# ArduOSD_Simple2222.net
KiCad netlist of a schematic drawn in EAGLE
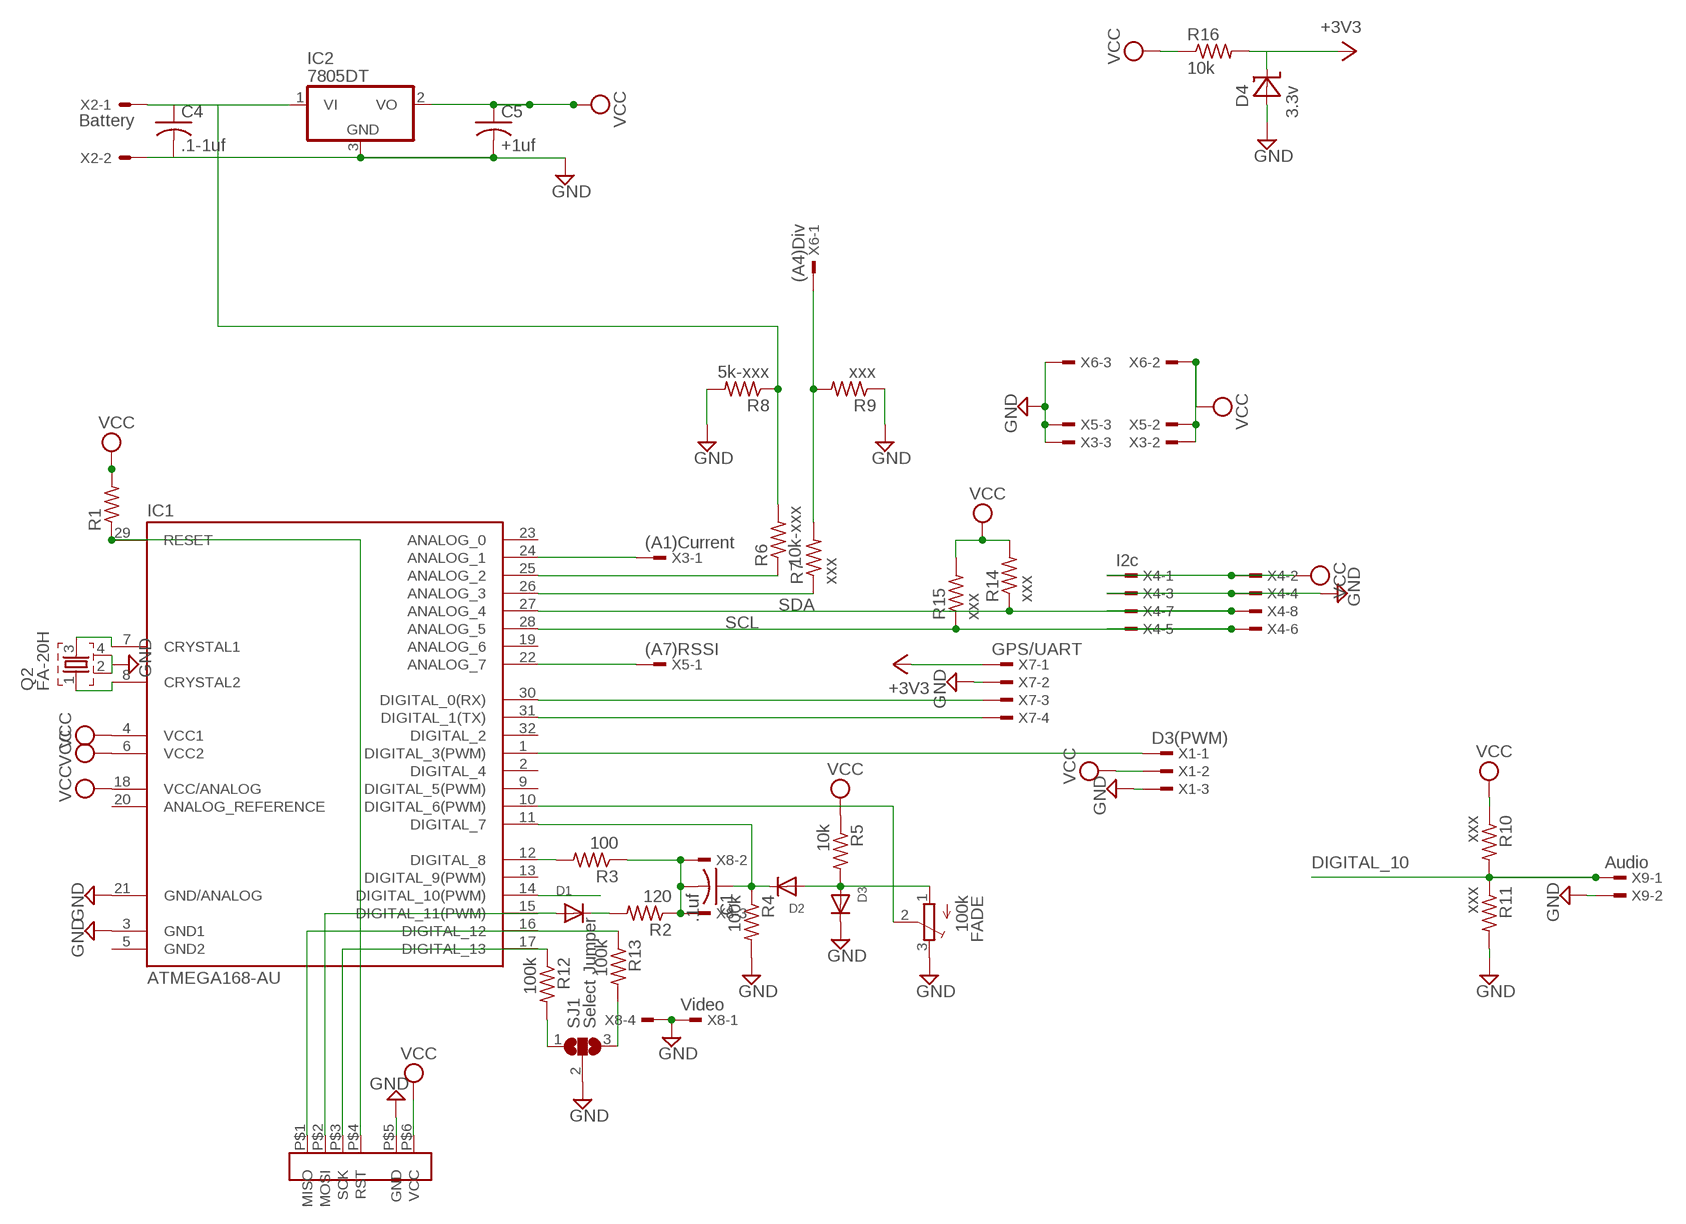
[diagram p0: schematic, sheet 1]

(export (version "E")
  (design (tool "Eeschema 10.0.6"))
  (components
    (comp (ref "C1")
      (value ".1uf")
      (footprint "eagle-import:C0805K")
      (libsource (lib "eagle-import") (part "C-USC0805K"))
    )
    (comp (ref "C4")
      (value ".1-1uf")
      (footprint "eagle-import:C0805K")
      (libsource (lib "eagle-import") (part "C-USC0805K"))
    )
    (comp (ref "C5")
      (value "+1uf")
      (footprint "eagle-import:C0805K")
      (libsource (lib "eagle-import") (part "C-USC0805K"))
    )
    (comp (ref "D1")
      (value "DIODESOT23_WAVE")
      (footprint "eagle-import:SOT23-W")
      (libsource (lib "eagle-import") (part "DIODESOT23_WAVE"))
    )
    (comp (ref "D2")
      (value "DIODESOT23_WAVE")
      (footprint "eagle-import:SOT23-W")
      (libsource (lib "eagle-import") (part "DIODESOT23_WAVE"))
    )
    (comp (ref "D3")
      (value "DIODESOT23_WAVE")
      (footprint "eagle-import:SOT23-W")
      (libsource (lib "eagle-import") (part "DIODESOT23_WAVE"))
    )
    (comp (ref "D4")
      (value "3.3v")
      (footprint "eagle-import:SOD-123")
      (libsource (lib "eagle-import") (part "ZENER_SOD123"))
    )
    (comp (ref "FADE")
      (value "100k")
      (footprint "eagle-import:TC33X")
      (libsource (lib "eagle-import") (part "TRIMPOTTC33X"))
    )
    (comp (ref "IC1")
      (value "ATMEGA168-AU")
      (footprint "eagle-import:TQFP32-08")
      (libsource (lib "eagle-import") (part "ATMEGA168-AU"))
    )
    (comp (ref "IC2")
      (value "7805DT")
      (footprint "eagle-import:TO252")
      (libsource (lib "eagle-import") (part "78DT05"))
    )
    (comp (ref "Q2")
      (value "FA-20H")
      (footprint "eagle-import:FA-20H")
      (libsource (lib "eagle-import") (part "FA-20H"))
    )
    (comp (ref "R1")
      (value "R-US_R0805")
      (footprint "eagle-import:R0805")
      (libsource (lib "eagle-import") (part "R-US_R0805"))
    )
    (comp (ref "R2")
      (value "120")
      (footprint "eagle-import:R0805")
      (libsource (lib "eagle-import") (part "R-US_R0805"))
    )
    (comp (ref "R3")
      (value "100")
      (footprint "eagle-import:R0805")
      (libsource (lib "eagle-import") (part "R-US_R0805"))
    )
    (comp (ref "R4")
      (value "100k")
      (footprint "eagle-import:R0805")
      (libsource (lib "eagle-import") (part "R-US_R0805"))
    )
    (comp (ref "R5")
      (value "10k")
      (footprint "eagle-import:R0805")
      (libsource (lib "eagle-import") (part "R-US_R0805"))
    )
    (comp (ref "R6")
      (value "10k-xxx")
      (footprint "eagle-import:R0805")
      (libsource (lib "eagle-import") (part "R-US_R0805"))
    )
    (comp (ref "R7")
      (value "xxx")
      (footprint "eagle-import:R0805")
      (libsource (lib "eagle-import") (part "R-US_R0805"))
    )
    (comp (ref "R8")
      (value "5k-xxx")
      (footprint "eagle-import:R0805")
      (libsource (lib "eagle-import") (part "R-US_R0805"))
    )
    (comp (ref "R9")
      (value "xxx")
      (footprint "eagle-import:R0805")
      (libsource (lib "eagle-import") (part "R-US_R0805"))
    )
    (comp (ref "R10")
      (value "xxx")
      (footprint "eagle-import:R0805")
      (libsource (lib "eagle-import") (part "R-US_R0805"))
    )
    (comp (ref "R11")
      (value "xxx")
      (footprint "eagle-import:R0805")
      (libsource (lib "eagle-import") (part "R-US_R0805"))
    )
    (comp (ref "R12")
      (value "100k")
      (footprint "eagle-import:R0805")
      (libsource (lib "eagle-import") (part "R-US_R0805"))
    )
    (comp (ref "R13")
      (value "100k")
      (footprint "eagle-import:R0805")
      (libsource (lib "eagle-import") (part "R-US_R0805"))
    )
    (comp (ref "R14")
      (value "xxx")
      (footprint "eagle-import:R0805")
      (libsource (lib "eagle-import") (part "R-US_R0805"))
    )
    (comp (ref "R15")
      (value "xxx")
      (footprint "eagle-import:R0805")
      (libsource (lib "eagle-import") (part "R-US_R0805"))
    )
    (comp (ref "R16")
      (value "10k")
      (footprint "eagle-import:R0805")
      (libsource (lib "eagle-import") (part "R-US_R0805"))
    )
    (comp (ref "SJ1")
      (value "Select Jumper")
      (footprint "eagle-import:SJ_2")
      (libsource (lib "eagle-import") (part "SJ2W"))
    )
    (comp (ref "U$1")
      (value "LIN_ISP")
      (footprint "eagle-import:LINEAR_ISP")
      (libsource (lib "eagle-import") (part "LIN_ISP"))
    )
    (comp (ref "X1")
      (value "D3(PWM)")
      (footprint "eagle-import:TSW-103-02-S-S")
      (fields (field (name "OC_FARNELL") "unknown") (field (name "OC_NEWARK") "unknown"))
      (libsource (lib "eagle-import") (part "TSW-103-02-S-S"))
    )
    (comp (ref "X2")
      (value "Battery")
      (footprint "eagle-import:22-23-2021")
      (fields (field (name "MF") "MOLEX") (field (name "MPN") "22-23-2021"))
      (libsource (lib "eagle-import") (part "22-23-2021"))
    )
    (comp (ref "X3")
      (value "(A1)Current")
      (footprint "eagle-import:TSW-103-02-S-S")
      (libsource (lib "eagle-import") (part "TSW-103-02-S-S"))
    )
    (comp (ref "X4")
      (value "I2c")
      (footprint "eagle-import:TSW-104-02-S-D-RA")
      (libsource (lib "eagle-import") (part "TSW-104-02-S-D-RA"))
    )
    (comp (ref "X5")
      (value "(A7)RSSI")
      (footprint "eagle-import:TSW-103-02-S-S")
      (libsource (lib "eagle-import") (part "TSW-103-02-S-S"))
    )
    (comp (ref "X6")
      (value "(A4)Div")
      (footprint "eagle-import:TSW-103-02-S-S")
      (fields (field (name "OC_FARNELL") "unknown") (field (name "OC_NEWARK") "unknown"))
      (libsource (lib "eagle-import") (part "TSW-103-02-S-S"))
    )
    (comp (ref "X7")
      (value "GPS/UART")
      (footprint "eagle-import:TSW-104-02-S-S-RA")
      (libsource (lib "eagle-import") (part "TSW-104-02-S-S-RA"))
    )
    (comp (ref "X8")
      (value "Video")
      (footprint "eagle-import:TSW-104-02-S-S-RA")
      (libsource (lib "eagle-import") (part "TSW-104-02-S-S-RA"))
    )
    (comp (ref "X9")
      (value "Audio")
      (footprint "eagle-import:TSW-102-02-S-S-RA")
      (fields (field (name "OC_FARNELL") "unknown") (field (name "OC_NEWARK") "unknown"))
      (libsource (lib "eagle-import") (part "TSW-102-02-S-S-RA"))
    )
  )
  (nets
    (net (code "1") (name "+3V3") (class "Default")
      (node (ref "D4") (pin "1") (pinfunction "C_1") (pintype "passive"))
      (node (ref "R16") (pin "2") (pinfunction "2_2") (pintype "passive"))
      (node (ref "X7") (pin "1") (pinfunction "1_1") (pintype "passive"))
    )
    (net (code "2") (name "/DIGITAL_10") (class "Default")
      (node (ref "IC1") (pin "14") (pinfunction "DIGITAL_10(PWM)_14") (pintype "bidirectional"))
      (node (ref "R10") (pin "2") (pinfunction "2_2") (pintype "passive"))
      (node (ref "R11") (pin "1") (pinfunction "1_1") (pintype "passive"))
      (node (ref "X9") (pin "1") (pinfunction "1_1") (pintype "passive"))
    )
    (net (code "3") (name "/GND2") (class "Default")
      (node (ref "IC1") (pin "5") (pinfunction "GND2_5") (pintype "power_in"))
    )
    (net (code "4") (name "/SCL") (class "Default")
      (node (ref "IC1") (pin "28") (pinfunction "ANALOG_5_28") (pintype "bidirectional"))
      (node (ref "R15") (pin "1") (pinfunction "1_1") (pintype "passive"))
      (node (ref "X4") (pin "5") (pinfunction "1_5") (pintype "passive"))
      (node (ref "X4") (pin "6") (pinfunction "1_6") (pintype "passive"))
    )
    (net (code "5") (name "/SDA") (class "Default")
      (node (ref "IC1") (pin "27") (pinfunction "ANALOG_4_27") (pintype "bidirectional"))
      (node (ref "R14") (pin "1") (pinfunction "1_1") (pintype "passive"))
      (node (ref "X4") (pin "7") (pinfunction "1_7") (pintype "passive"))
      (node (ref "X4") (pin "8") (pinfunction "1_8") (pintype "passive"))
    )
    (net (code "6") (name "GND") (class "Default")
      (node (ref "C4") (pin "2") (pinfunction "2_2") (pintype "passive"))
      (node (ref "C5") (pin "2") (pinfunction "2_2") (pintype "passive"))
      (node (ref "D3") (pin "3") (pinfunction "C_3") (pintype "passive"))
      (node (ref "D4") (pin "2") (pinfunction "A_2") (pintype "passive"))
      (node (ref "FADE") (pin "3") (pinfunction "E_3") (pintype "passive"))
      (node (ref "IC1") (pin "21") (pinfunction "GND/ANALOG_21") (pintype "power_in"))
      (node (ref "IC1") (pin "3") (pinfunction "GND1_3") (pintype "power_in"))
      (node (ref "IC2") (pin "3") (pinfunction "GND_3") (pintype "passive"))
      (node (ref "Q2") (pin "2") (pinfunction "2_2") (pintype "passive"))
      (node (ref "Q2") (pin "4") (pinfunction "4_4") (pintype "passive"))
      (node (ref "R11") (pin "2") (pinfunction "2_2") (pintype "passive"))
      (node (ref "R4") (pin "2") (pinfunction "2_2") (pintype "passive"))
      (node (ref "R8") (pin "2") (pinfunction "2_2") (pintype "passive"))
      (node (ref "R9") (pin "1") (pinfunction "1_1") (pintype "passive"))
      (node (ref "SJ1") (pin "2") (pinfunction "2_2") (pintype "passive"))
      (node (ref "U$1") (pin "P$5") (pinfunction "GND_P$5") (pintype "bidirectional"))
      (node (ref "X1") (pin "3") (pinfunction "1_3") (pintype "passive"))
      (node (ref "X2") (pin "2") (pinfunction "S_2") (pintype "passive"))
      (node (ref "X3") (pin "3") (pinfunction "1_3") (pintype "passive"))
      (node (ref "X4") (pin "3") (pinfunction "1_3") (pintype "passive"))
      (node (ref "X4") (pin "4") (pinfunction "1_4") (pintype "passive"))
      (node (ref "X5") (pin "3") (pinfunction "1_3") (pintype "passive"))
      (node (ref "X6") (pin "3") (pinfunction "1_3") (pintype "passive"))
      (node (ref "X7") (pin "2") (pinfunction "1_2") (pintype "passive"))
      (node (ref "X8") (pin "1") (pinfunction "1_1") (pintype "passive"))
      (node (ref "X8") (pin "4") (pinfunction "1_4") (pintype "passive"))
      (node (ref "X9") (pin "2") (pinfunction "1_2") (pintype "passive"))
    )
    (net (code "7") (name "Net-(D1-A)") (class "Default")
      (node (ref "D1") (pin "1") (pinfunction "A_1") (pintype "passive"))
      (node (ref "IC1") (pin "15") (pinfunction "DIGITAL_11(PWM)_15") (pintype "bidirectional"))
      (node (ref "U$1") (pin "P$2") (pinfunction "MOSI_P$2") (pintype "bidirectional"))
    )
    (net (code "8") (name "Net-(D1-C)") (class "Default")
      (node (ref "D1") (pin "3") (pinfunction "C_3") (pintype "passive"))
      (node (ref "R2") (pin "2") (pinfunction "2_2") (pintype "passive"))
    )
    (net (code "9") (name "Net-(D2-A)") (class "Default")
      (node (ref "D2") (pin "1") (pinfunction "A_1") (pintype "passive"))
      (node (ref "D3") (pin "1") (pinfunction "A_1") (pintype "passive"))
      (node (ref "FADE") (pin "1") (pinfunction "A_1") (pintype "passive"))
      (node (ref "R5") (pin "2") (pinfunction "2_2") (pintype "passive"))
    )
    (net (code "10") (name "Net-(D2-C)") (class "Default")
      (node (ref "C1") (pin "1") (pinfunction "1_1") (pintype "passive"))
      (node (ref "D2") (pin "3") (pinfunction "C_3") (pintype "passive"))
      (node (ref "IC1") (pin "11") (pinfunction "DIGITAL_7_11") (pintype "bidirectional"))
      (node (ref "R4") (pin "1") (pinfunction "1_1") (pintype "passive"))
    )
    (net (code "11") (name "Net-(FADE-S)") (class "Default")
      (node (ref "FADE") (pin "2") (pinfunction "S_2") (pintype "passive"))
      (node (ref "IC1") (pin "10") (pinfunction "DIGITAL_6(PWM)_10") (pintype "bidirectional"))
    )
    (net (code "12") (name "Net-(IC1-ANALOG_1)") (class "Default")
      (node (ref "IC1") (pin "24") (pinfunction "ANALOG_1_24") (pintype "bidirectional"))
      (node (ref "X3") (pin "1") (pinfunction "1_1") (pintype "passive"))
    )
    (net (code "13") (name "Net-(IC1-ANALOG_2)") (class "Default")
      (node (ref "IC1") (pin "25") (pinfunction "ANALOG_2_25") (pintype "bidirectional"))
      (node (ref "R6") (pin "1") (pinfunction "1_1") (pintype "passive"))
    )
    (net (code "14") (name "Net-(IC1-ANALOG_3)") (class "Default")
      (node (ref "IC1") (pin "26") (pinfunction "ANALOG_3_26") (pintype "bidirectional"))
      (node (ref "R7") (pin "1") (pinfunction "1_1") (pintype "passive"))
    )
    (net (code "15") (name "Net-(IC1-ANALOG_7)") (class "Default")
      (node (ref "IC1") (pin "22") (pinfunction "ANALOG_7_22") (pintype "passive"))
      (node (ref "X5") (pin "1") (pinfunction "1_1") (pintype "passive"))
    )
    (net (code "16") (name "Net-(IC1-CRYSTAL1)") (class "Default")
      (node (ref "IC1") (pin "7") (pinfunction "CRYSTAL1_7") (pintype "bidirectional"))
      (node (ref "Q2") (pin "3") (pinfunction "3_3") (pintype "passive"))
    )
    (net (code "17") (name "Net-(IC1-CRYSTAL2)") (class "Default")
      (node (ref "IC1") (pin "8") (pinfunction "CRYSTAL2_8") (pintype "bidirectional"))
      (node (ref "Q2") (pin "1") (pinfunction "1_1") (pintype "passive"))
    )
    (net (code "18") (name "Net-(IC1-DIGITAL_0(RX))") (class "Default")
      (node (ref "IC1") (pin "30") (pinfunction "DIGITAL_0(RX)_30") (pintype "bidirectional"))
      (node (ref "X7") (pin "3") (pinfunction "1_3") (pintype "passive"))
    )
    (net (code "19") (name "Net-(IC1-DIGITAL_1(TX))") (class "Default")
      (node (ref "IC1") (pin "31") (pinfunction "DIGITAL_1(TX)_31") (pintype "bidirectional"))
      (node (ref "X7") (pin "4") (pinfunction "1_4") (pintype "passive"))
    )
    (net (code "20") (name "Net-(IC1-DIGITAL_3(PWM))") (class "Default")
      (node (ref "IC1") (pin "1") (pinfunction "DIGITAL_3(PWM)_1") (pintype "bidirectional"))
      (node (ref "X1") (pin "1") (pinfunction "1_1") (pintype "passive"))
    )
    (net (code "21") (name "Net-(IC1-DIGITAL_8)") (class "Default")
      (node (ref "IC1") (pin "12") (pinfunction "DIGITAL_8_12") (pintype "bidirectional"))
      (node (ref "R3") (pin "2") (pinfunction "2_2") (pintype "passive"))
    )
    (net (code "22") (name "Net-(IC1-DIGITAL_12)") (class "Default")
      (node (ref "IC1") (pin "16") (pinfunction "DIGITAL_12_16") (pintype "bidirectional"))
      (node (ref "R13") (pin "1") (pinfunction "1_1") (pintype "passive"))
      (node (ref "U$1") (pin "P$1") (pinfunction "MISO_P$1") (pintype "bidirectional"))
    )
    (net (code "23") (name "Net-(IC1-DIGITAL_13)") (class "Default")
      (node (ref "IC1") (pin "17") (pinfunction "DIGITAL_13_17") (pintype "bidirectional"))
      (node (ref "R12") (pin "1") (pinfunction "1_1") (pintype "passive"))
      (node (ref "U$1") (pin "P$3") (pinfunction "SCK_P$3") (pintype "bidirectional"))
    )
    (net (code "24") (name "Net-(IC1-RESET)") (class "Default")
      (node (ref "IC1") (pin "29") (pinfunction "RESET_29") (pintype "bidirectional"))
      (node (ref "R1") (pin "1") (pinfunction "1_1") (pintype "passive"))
      (node (ref "U$1") (pin "P$4") (pinfunction "RST_P$4") (pintype "bidirectional"))
    )
    (net (code "25") (name "Net-(IC2-VI)") (class "Default")
      (node (ref "C4") (pin "1") (pinfunction "1_1") (pintype "passive"))
      (node (ref "IC2") (pin "1") (pinfunction "VI_1") (pintype "input"))
      (node (ref "R6") (pin "2") (pinfunction "2_2") (pintype "passive"))
      (node (ref "R8") (pin "1") (pinfunction "1_1") (pintype "passive"))
      (node (ref "X2") (pin "1") (pinfunction "S_1") (pintype "passive"))
    )
    (net (code "26") (name "Net-(R7-Pad2)") (class "Default")
      (node (ref "R7") (pin "2") (pinfunction "2_2") (pintype "passive"))
      (node (ref "R9") (pin "2") (pinfunction "2_2") (pintype "passive"))
      (node (ref "X6") (pin "1") (pinfunction "1_1") (pintype "passive"))
    )
    (net (code "27") (name "Net-(R12-Pad2)") (class "Default")
      (node (ref "R12") (pin "2") (pinfunction "2_2") (pintype "passive"))
      (node (ref "SJ1") (pin "1") (pinfunction "1_1") (pintype "passive"))
    )
    (net (code "28") (name "Net-(R13-Pad2)") (class "Default")
      (node (ref "R13") (pin "2") (pinfunction "2_2") (pintype "passive"))
      (node (ref "SJ1") (pin "3") (pinfunction "3_3") (pintype "passive"))
    )
    (net (code "29") (name "Net-(X8B-1)") (class "Default")
      (node (ref "C1") (pin "2") (pinfunction "2_2") (pintype "passive"))
      (node (ref "R2") (pin "1") (pinfunction "1_1") (pintype "passive"))
      (node (ref "R3") (pin "1") (pinfunction "1_1") (pintype "passive"))
      (node (ref "X8") (pin "2") (pinfunction "1_2") (pintype "passive"))
      (node (ref "X8") (pin "3") (pinfunction "1_3") (pintype "passive"))
    )
    (net (code "30") (name "VCC") (class "Default")
      (node (ref "C5") (pin "1") (pinfunction "1_1") (pintype "passive"))
      (node (ref "IC1") (pin "18") (pinfunction "VCC/ANALOG_18") (pintype "passive"))
      (node (ref "IC1") (pin "4") (pinfunction "VCC1_4") (pintype "power_in"))
      (node (ref "IC1") (pin "6") (pinfunction "VCC2_6") (pintype "power_in"))
      (node (ref "IC2") (pin "2") (pinfunction "VO_2") (pintype "passive"))
      (node (ref "R1") (pin "2") (pinfunction "2_2") (pintype "passive"))
      (node (ref "R10") (pin "1") (pinfunction "1_1") (pintype "passive"))
      (node (ref "R14") (pin "2") (pinfunction "2_2") (pintype "passive"))
      (node (ref "R15") (pin "2") (pinfunction "2_2") (pintype "passive"))
      (node (ref "R16") (pin "1") (pinfunction "1_1") (pintype "passive"))
      (node (ref "R5") (pin "1") (pinfunction "1_1") (pintype "passive"))
      (node (ref "U$1") (pin "P$6") (pinfunction "VCC_P$6") (pintype "bidirectional"))
      (node (ref "X1") (pin "2") (pinfunction "1_2") (pintype "passive"))
      (node (ref "X3") (pin "2") (pinfunction "1_2") (pintype "passive"))
      (node (ref "X4") (pin "1") (pinfunction "1_1") (pintype "passive"))
      (node (ref "X4") (pin "2") (pinfunction "1_2") (pintype "passive"))
      (node (ref "X5") (pin "2") (pinfunction "1_2") (pintype "passive"))
      (node (ref "X6") (pin "2") (pinfunction "1_2") (pintype "passive"))
    )
    (net (code "31") (name "unconnected-(IC1-ANALOG_0-Pad23)") (class "Default")
      (node (ref "IC1") (pin "23") (pinfunction "ANALOG_0_23") (pintype "bidirectional"))
    )
    (net (code "32") (name "unconnected-(IC1-ANALOG_6-Pad19)") (class "Default")
      (node (ref "IC1") (pin "19") (pinfunction "ANALOG_6_19") (pintype "passive"))
    )
    (net (code "33") (name "unconnected-(IC1-ANALOG_REFERENCE-Pad20)") (class "Default")
      (node (ref "IC1") (pin "20") (pinfunction "ANALOG_REFERENCE_20") (pintype "passive"))
    )
    (net (code "34") (name "unconnected-(IC1-DIGITAL_2-Pad32)") (class "Default")
      (node (ref "IC1") (pin "32") (pinfunction "DIGITAL_2_32") (pintype "bidirectional"))
    )
    (net (code "35") (name "unconnected-(IC1-DIGITAL_4-Pad2)") (class "Default")
      (node (ref "IC1") (pin "2") (pinfunction "DIGITAL_4_2") (pintype "bidirectional"))
    )
    (net (code "36") (name "unconnected-(IC1-DIGITAL_5(PWM)-Pad9)") (class "Default")
      (node (ref "IC1") (pin "9") (pinfunction "DIGITAL_5(PWM)_9") (pintype "bidirectional"))
    )
    (net (code "37") (name "unconnected-(IC1-DIGITAL_9(PWM)-Pad13)") (class "Default")
      (node (ref "IC1") (pin "13") (pinfunction "DIGITAL_9(PWM)_13") (pintype "bidirectional"))
    )
  )
)
